# iblock-energy-monitor.net
KiCad netlist of a schematic drawn in EAGLE
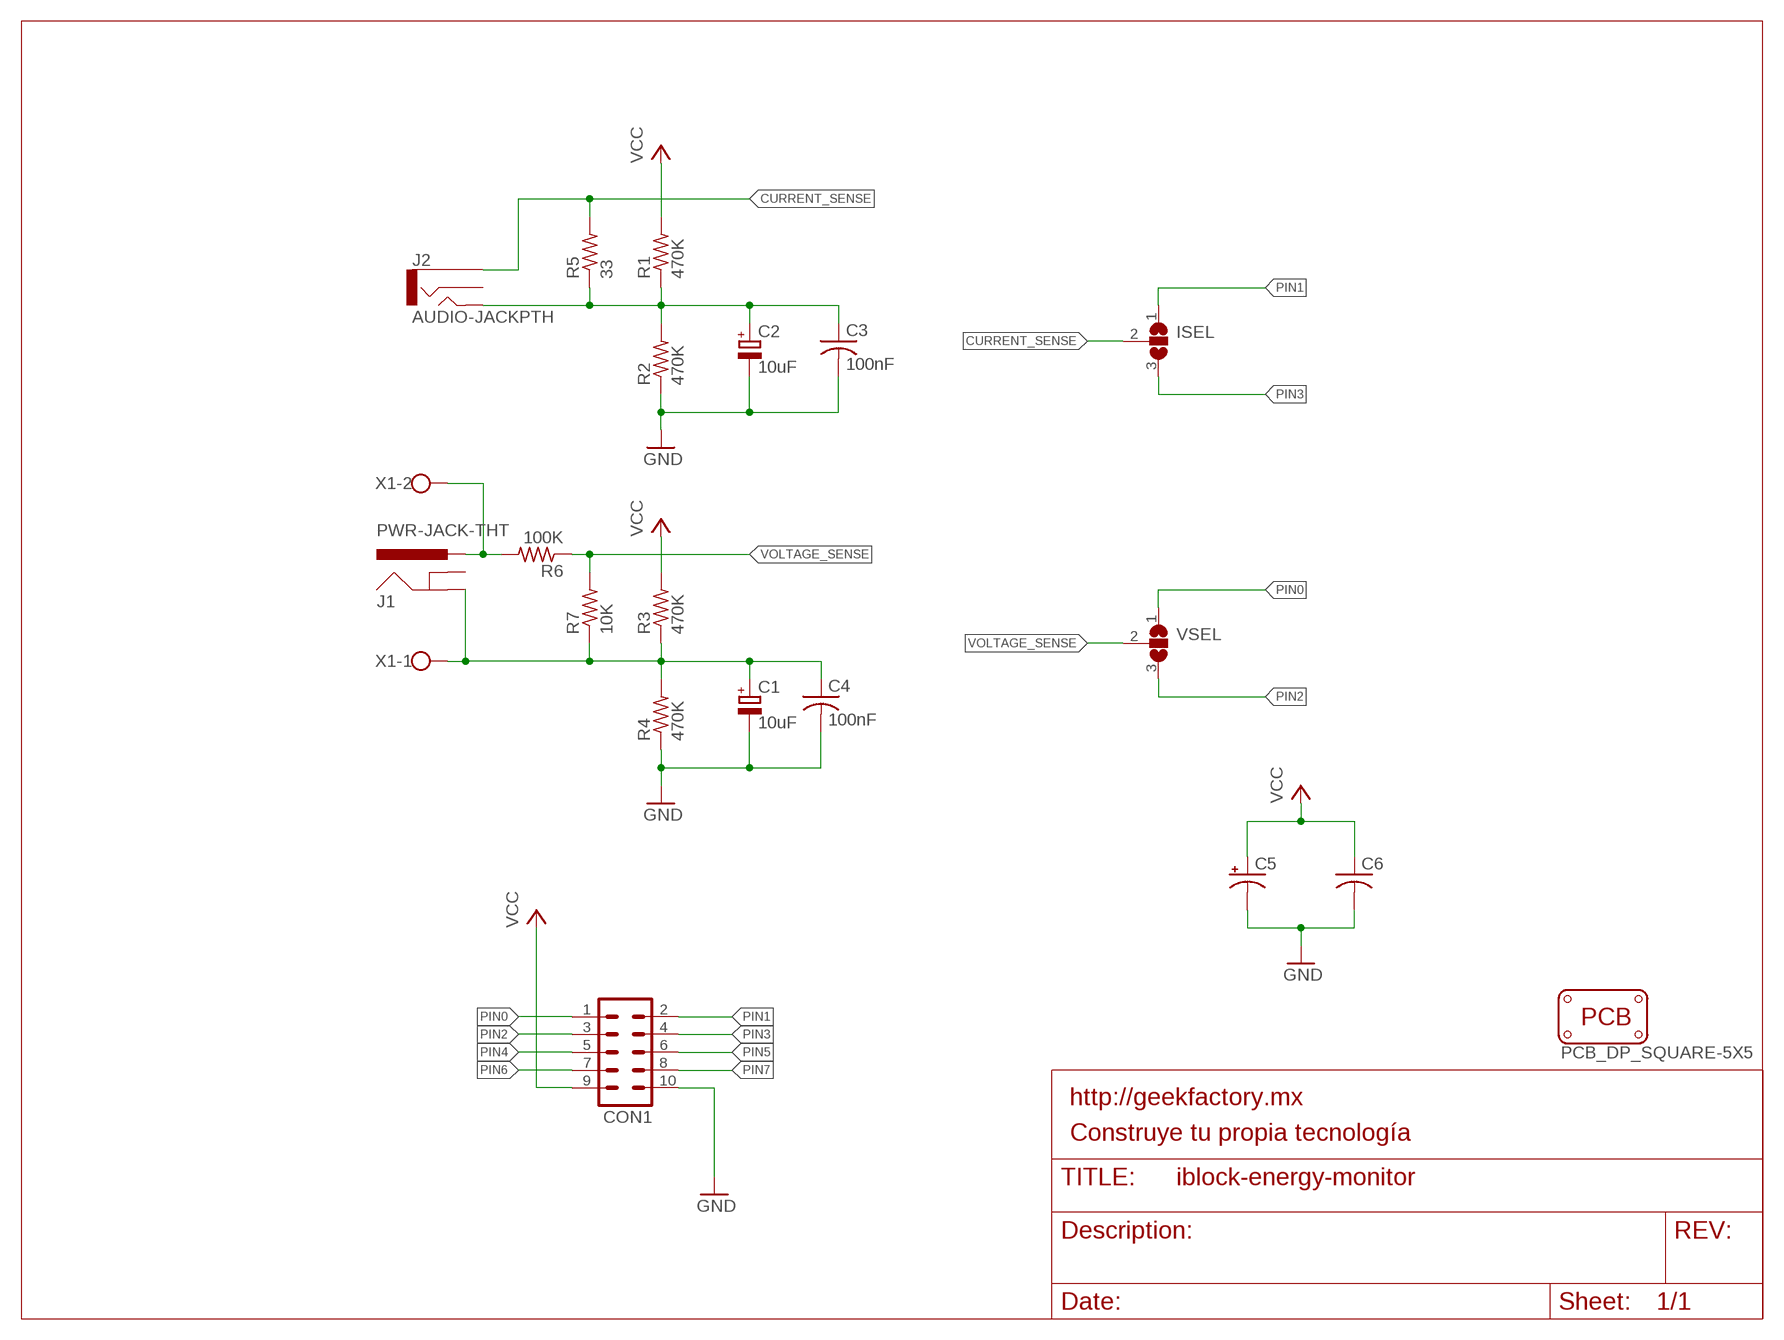
[diagram p0: schematic, sheet 1]

(export (version "E")
  (design (tool "Eeschema 10.0.6"))
  (components
    (comp (ref "C1")
      (value "10uF")
      (footprint "eagle-import:E2,5-5")
      (libsource (lib "eagle-import") (part "CPOL-EUE2.5-5"))
    )
    (comp (ref "C2")
      (value "10uF")
      (footprint "eagle-import:E2,5-5")
      (libsource (lib "eagle-import") (part "CPOL-EUE2.5-5"))
    )
    (comp (ref "C3")
      (value "100nF")
      (footprint "eagle-import:C050-024X044")
      (libsource (lib "eagle-import") (part "C-US050-024X044"))
    )
    (comp (ref "C4")
      (value "100nF")
      (footprint "eagle-import:C050-024X044")
      (libsource (lib "eagle-import") (part "C-US050-024X044"))
    )
    (comp (ref "C5")
      (value "CPOL-USE3.5-8")
      (footprint "eagle-import:E3,5-8")
      (libsource (lib "eagle-import") (part "CPOL-USE3.5-8"))
    )
    (comp (ref "C6")
      (value "C-US050-024X044")
      (footprint "eagle-import:C050-024X044")
      (libsource (lib "eagle-import") (part "C-US050-024X044"))
    )
    (comp (ref "CON1")
      (value "MA05-2S")
      (footprint "eagle-import:MA05-2")
      (libsource (lib "eagle-import") (part "MA05-2S"))
    )
    (comp (ref "ISEL")
      (value "SJ2W")
      (footprint "eagle-import:SJ_2")
      (libsource (lib "eagle-import") (part "SJ2W"))
    )
    (comp (ref "J1")
      (value "PWR-JACK-THT")
      (footprint "eagle-import:THT-PWR-JACK")
      (libsource (lib "eagle-import") (part "PWR-JACK-THT"))
    )
    (comp (ref "J2")
      (value "AUDIO-JACKPTH")
      (footprint "eagle-import:AUDIO-JACK")
      (libsource (lib "eagle-import") (part "AUDIO-JACKPTH"))
    )
    (comp (ref "PCB1")
      (value "PCB_DP_SQUARE-5X5")
      (footprint "eagle-import:DP5050_V1")
      (libsource (lib "eagle-import") (part "PCB_DP_SQUARE-5X5"))
    )
    (comp (ref "R1")
      (value "470K")
      (footprint "eagle-import:0207_10")
      (libsource (lib "eagle-import") (part "R-US_0207/10"))
    )
    (comp (ref "R2")
      (value "470K")
      (footprint "eagle-import:0207_10")
      (libsource (lib "eagle-import") (part "R-US_0207/10"))
    )
    (comp (ref "R3")
      (value "470K")
      (footprint "eagle-import:0207_10")
      (libsource (lib "eagle-import") (part "R-US_0207/10"))
    )
    (comp (ref "R4")
      (value "470K")
      (footprint "eagle-import:0207_10")
      (libsource (lib "eagle-import") (part "R-US_0207/10"))
    )
    (comp (ref "R5")
      (value "33")
      (footprint "eagle-import:0207_10")
      (libsource (lib "eagle-import") (part "R-US_0207/10"))
    )
    (comp (ref "R6")
      (value "100K")
      (footprint "eagle-import:0207_10")
      (libsource (lib "eagle-import") (part "R-US_0207/10"))
    )
    (comp (ref "R7")
      (value "10K")
      (footprint "eagle-import:0207_10")
      (libsource (lib "eagle-import") (part "R-US_0207/10"))
    )
    (comp (ref "VSEL")
      (value "SJ2W")
      (footprint "eagle-import:SJ_2")
      (libsource (lib "eagle-import") (part "SJ2W"))
    )
    (comp (ref "X1")
      (value "W237-102")
      (footprint "eagle-import:W237-102")
      (fields (field (name "MPN") "237-102"))
      (libsource (lib "eagle-import") (part "W237-102"))
    )
  )
  (nets
    (net (code "1") (name "CURRENT_SENSE") (class "Default")
      (node (ref "ISEL") (pin "2") (pinfunction "2_2") (pintype "passive"))
      (node (ref "J2") (pin "1") (pinfunction "1_1") (pintype "bidirectional"))
      (node (ref "R5") (pin "2") (pinfunction "2_2") (pintype "passive"))
    )
    (net (code "2") (name "GND") (class "Default")
      (node (ref "C1") (pin "-") (pinfunction "-_-") (pintype "passive"))
      (node (ref "C2") (pin "-") (pinfunction "-_-") (pintype "passive"))
      (node (ref "C3") (pin "2") (pinfunction "2_2") (pintype "passive"))
      (node (ref "C4") (pin "2") (pinfunction "2_2") (pintype "passive"))
      (node (ref "C5") (pin "-") (pinfunction "-_-") (pintype "passive"))
      (node (ref "C6") (pin "2") (pinfunction "2_2") (pintype "passive"))
      (node (ref "CON1") (pin "10") (pinfunction "10_10") (pintype "passive"))
      (node (ref "R2") (pin "1") (pinfunction "1_1") (pintype "passive"))
      (node (ref "R4") (pin "1") (pinfunction "1_1") (pintype "passive"))
    )
    (net (code "3") (name "Net-(C2-Pad+)") (class "Default")
      (node (ref "C2") (pin "+") (pinfunction "+_+") (pintype "passive"))
      (node (ref "C3") (pin "1") (pinfunction "1_1") (pintype "passive"))
      (node (ref "J2") (pin "5") (pinfunction "5_5") (pintype "bidirectional"))
      (node (ref "R1") (pin "1") (pinfunction "1_1") (pintype "passive"))
      (node (ref "R2") (pin "2") (pinfunction "2_2") (pintype "passive"))
      (node (ref "R5") (pin "1") (pinfunction "1_1") (pintype "passive"))
    )
    (net (code "4") (name "Net-(X1A-KL)") (class "Default")
      (node (ref "C1") (pin "+") (pinfunction "+_+") (pintype "passive"))
      (node (ref "C4") (pin "1") (pinfunction "1_1") (pintype "passive"))
      (node (ref "J1") (pin "GND") (pinfunction "GND_GND") (pintype "passive"))
      (node (ref "R3") (pin "1") (pinfunction "1_1") (pintype "passive"))
      (node (ref "R4") (pin "2") (pinfunction "2_2") (pintype "passive"))
      (node (ref "R7") (pin "1") (pinfunction "1_1") (pintype "passive"))
      (node (ref "X1") (pin "1") (pinfunction "KL_1") (pintype "passive"))
    )
    (net (code "5") (name "Net-(X1B-KL)") (class "Default")
      (node (ref "J1") (pin "PWR") (pinfunction "PWR_PWR") (pintype "passive"))
      (node (ref "R6") (pin "2") (pinfunction "2_2") (pintype "passive"))
      (node (ref "X1") (pin "2") (pinfunction "KL_2") (pintype "passive"))
    )
    (net (code "6") (name "PIN0") (class "Default")
      (node (ref "CON1") (pin "1") (pinfunction "1_1") (pintype "passive"))
      (node (ref "VSEL") (pin "1") (pinfunction "1_1") (pintype "passive"))
    )
    (net (code "7") (name "PIN1") (class "Default")
      (node (ref "CON1") (pin "2") (pinfunction "2_2") (pintype "passive"))
      (node (ref "ISEL") (pin "1") (pinfunction "1_1") (pintype "passive"))
    )
    (net (code "8") (name "PIN2") (class "Default")
      (node (ref "CON1") (pin "3") (pinfunction "3_3") (pintype "passive"))
      (node (ref "VSEL") (pin "3") (pinfunction "3_3") (pintype "passive"))
    )
    (net (code "9") (name "PIN3") (class "Default")
      (node (ref "CON1") (pin "4") (pinfunction "4_4") (pintype "passive"))
      (node (ref "ISEL") (pin "3") (pinfunction "3_3") (pintype "passive"))
    )
    (net (code "10") (name "PIN4") (class "Default")
      (node (ref "CON1") (pin "5") (pinfunction "5_5") (pintype "passive"))
    )
    (net (code "11") (name "PIN5") (class "Default")
      (node (ref "CON1") (pin "6") (pinfunction "6_6") (pintype "passive"))
    )
    (net (code "12") (name "PIN6") (class "Default")
      (node (ref "CON1") (pin "7") (pinfunction "7_7") (pintype "passive"))
    )
    (net (code "13") (name "PIN7") (class "Default")
      (node (ref "CON1") (pin "8") (pinfunction "8_8") (pintype "passive"))
    )
    (net (code "14") (name "VCC") (class "Default")
      (node (ref "C5") (pin "+") (pinfunction "+_+") (pintype "passive"))
      (node (ref "C6") (pin "1") (pinfunction "1_1") (pintype "passive"))
      (node (ref "CON1") (pin "9") (pinfunction "9_9") (pintype "passive"))
      (node (ref "R1") (pin "2") (pinfunction "2_2") (pintype "passive"))
      (node (ref "R3") (pin "2") (pinfunction "2_2") (pintype "passive"))
    )
    (net (code "15") (name "VOLTAGE_SENSE") (class "Default")
      (node (ref "R6") (pin "1") (pinfunction "1_1") (pintype "passive"))
      (node (ref "R7") (pin "2") (pinfunction "2_2") (pintype "passive"))
      (node (ref "VSEL") (pin "2") (pinfunction "2_2") (pintype "passive"))
    )
    (net (code "16") (name "unconnected-(J1-PadGNDBREAK)") (class "Default")
      (node (ref "J1") (pin "GNDBREAK") (pinfunction "GNDBREAK_GNDBREAK") (pintype "passive"))
    )
    (net (code "17") (name "unconnected-(J2-Pad2)") (class "Default")
      (node (ref "J2") (pin "2") (pinfunction "2_2") (pintype "bidirectional"))
    )
  )
)
